# LCD_Screen.net
KiCad netlist of a schematic drawn in Altium Designer
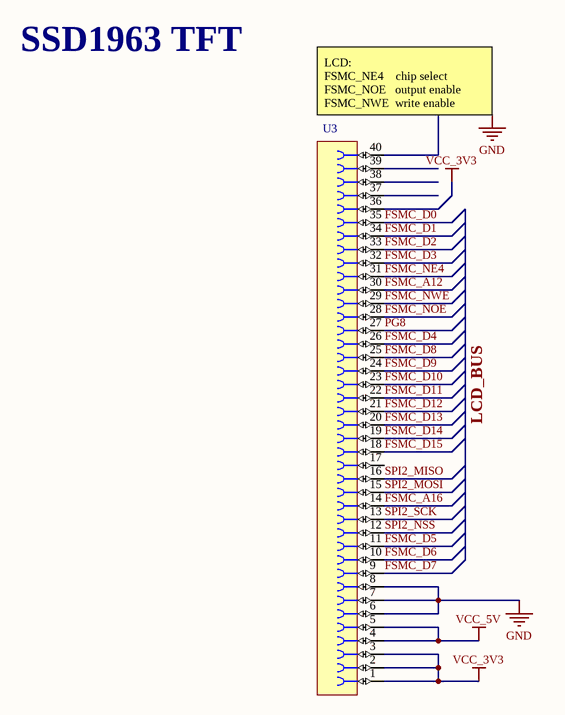
[diagram p0: LCD Screen.SchDoc]

(export (version "E")
  (design (tool "Eeschema 10.0.6"))
  (components
    (comp (ref "U3")
      (value "~")
      (description "Connector 40 Female")
      (libsource (lib "Connectors") (part "Connector 40 Female"))
    )
  )
  (nets
    (net (code "2") (name "/FSMC_A12") (class "Default")
      (node (ref "U3") (pin "30") (pinfunction "30_30") (pintype "bidirectional"))
    )
    (net (code "3") (name "/FSMC_A16") (class "Default")
      (node (ref "U3") (pin "14") (pinfunction "14_14") (pintype "bidirectional"))
    )
    (net (code "4") (name "/FSMC_D0") (class "Default")
      (node (ref "U3") (pin "35") (pinfunction "35_35") (pintype "bidirectional"))
    )
    (net (code "5") (name "/FSMC_D1") (class "Default")
      (node (ref "U3") (pin "34") (pinfunction "34_34") (pintype "bidirectional"))
    )
    (net (code "6") (name "/FSMC_D2") (class "Default")
      (node (ref "U3") (pin "33") (pinfunction "33_33") (pintype "bidirectional"))
    )
    (net (code "7") (name "/FSMC_D3") (class "Default")
      (node (ref "U3") (pin "32") (pinfunction "32_32") (pintype "bidirectional"))
    )
    (net (code "8") (name "/FSMC_D4") (class "Default")
      (node (ref "U3") (pin "26") (pinfunction "26_26") (pintype "bidirectional"))
    )
    (net (code "9") (name "/FSMC_D5") (class "Default")
      (node (ref "U3") (pin "11") (pinfunction "11_11") (pintype "bidirectional"))
    )
    (net (code "10") (name "/FSMC_D6") (class "Default")
      (node (ref "U3") (pin "10") (pinfunction "10_10") (pintype "bidirectional"))
    )
    (net (code "11") (name "/FSMC_D7") (class "Default")
      (node (ref "U3") (pin "9") (pinfunction "9_9") (pintype "bidirectional"))
    )
    (net (code "12") (name "/FSMC_D8") (class "Default")
      (node (ref "U3") (pin "25") (pinfunction "25_25") (pintype "bidirectional"))
    )
    (net (code "13") (name "/FSMC_D9") (class "Default")
      (node (ref "U3") (pin "24") (pinfunction "24_24") (pintype "bidirectional"))
    )
    (net (code "14") (name "/FSMC_D10") (class "Default")
      (node (ref "U3") (pin "23") (pinfunction "23_23") (pintype "bidirectional"))
    )
    (net (code "15") (name "/FSMC_D11") (class "Default")
      (node (ref "U3") (pin "22") (pinfunction "22_22") (pintype "bidirectional"))
    )
    (net (code "16") (name "/FSMC_D12") (class "Default")
      (node (ref "U3") (pin "21") (pinfunction "21_21") (pintype "bidirectional"))
    )
    (net (code "17") (name "/FSMC_D13") (class "Default")
      (node (ref "U3") (pin "20") (pinfunction "20_20") (pintype "bidirectional"))
    )
    (net (code "18") (name "/FSMC_D14") (class "Default")
      (node (ref "U3") (pin "19") (pinfunction "19_19") (pintype "bidirectional"))
    )
    (net (code "19") (name "/FSMC_D15") (class "Default")
      (node (ref "U3") (pin "18") (pinfunction "18_18") (pintype "bidirectional"))
    )
    (net (code "20") (name "/FSMC_NE4") (class "Default")
      (node (ref "U3") (pin "31") (pinfunction "31_31") (pintype "bidirectional"))
    )
    (net (code "21") (name "/FSMC_NOE") (class "Default")
      (node (ref "U3") (pin "28") (pinfunction "28_28") (pintype "bidirectional"))
    )
    (net (code "22") (name "/FSMC_NWE") (class "Default")
      (node (ref "U3") (pin "29") (pinfunction "29_29") (pintype "bidirectional"))
    )
    (net (code "23") (name "/PG8") (class "Default")
      (node (ref "U3") (pin "27") (pinfunction "27_27") (pintype "bidirectional"))
    )
    (net (code "24") (name "/SPI2_MISO") (class "Default")
      (node (ref "U3") (pin "16") (pinfunction "16_16") (pintype "bidirectional"))
    )
    (net (code "25") (name "/SPI2_MOSI") (class "Default")
      (node (ref "U3") (pin "15") (pinfunction "15_15") (pintype "bidirectional"))
    )
    (net (code "26") (name "/SPI2_NSS") (class "Default")
      (node (ref "U3") (pin "12") (pinfunction "12_12") (pintype "bidirectional"))
    )
    (net (code "27") (name "/SPI2_SCK") (class "Default")
      (node (ref "U3") (pin "13") (pinfunction "13_13") (pintype "bidirectional"))
    )
    (net (code "29") (name "GND") (class "Default")
      (node (ref "U3") (pin "40") (pinfunction "40_40") (pintype "bidirectional"))
      (node (ref "U3") (pin "6") (pinfunction "6_6") (pintype "bidirectional"))
      (node (ref "U3") (pin "7") (pinfunction "7_7") (pintype "bidirectional"))
      (node (ref "U3") (pin "8") (pinfunction "8_8") (pintype "bidirectional"))
    )
    (net (code "30") (name "VCC_3V3") (class "Default")
      (node (ref "U3") (pin "1") (pinfunction "1_1") (pintype "bidirectional"))
      (node (ref "U3") (pin "2") (pinfunction "2_2") (pintype "bidirectional"))
      (node (ref "U3") (pin "3") (pinfunction "3_3") (pintype "bidirectional"))
      (node (ref "U3") (pin "36") (pinfunction "36_36") (pintype "bidirectional"))
    )
    (net (code "31") (name "VCC_5V") (class "Default")
      (node (ref "U3") (pin "4") (pinfunction "4_4") (pintype "bidirectional"))
      (node (ref "U3") (pin "5") (pinfunction "5_5") (pintype "bidirectional"))
    )
    (net (code "32") (name "unconnected-(U3-Pad17)") (class "Default")
      (node (ref "U3") (pin "17") (pinfunction "17_17") (pintype "bidirectional"))
    )
    (net (code "33") (name "unconnected-(U3-Pad37)") (class "Default")
      (node (ref "U3") (pin "37") (pinfunction "37_37") (pintype "bidirectional"))
    )
    (net (code "34") (name "unconnected-(U3-Pad38)") (class "Default")
      (node (ref "U3") (pin "38") (pinfunction "38_38") (pintype "bidirectional"))
    )
    (net (code "35") (name "unconnected-(U3-Pad39)") (class "Default")
      (node (ref "U3") (pin "39") (pinfunction "39_39") (pintype "bidirectional"))
    )
  )
)
